# Schematic5.net
KiCad netlist of a schematic drawn in Altium Designer
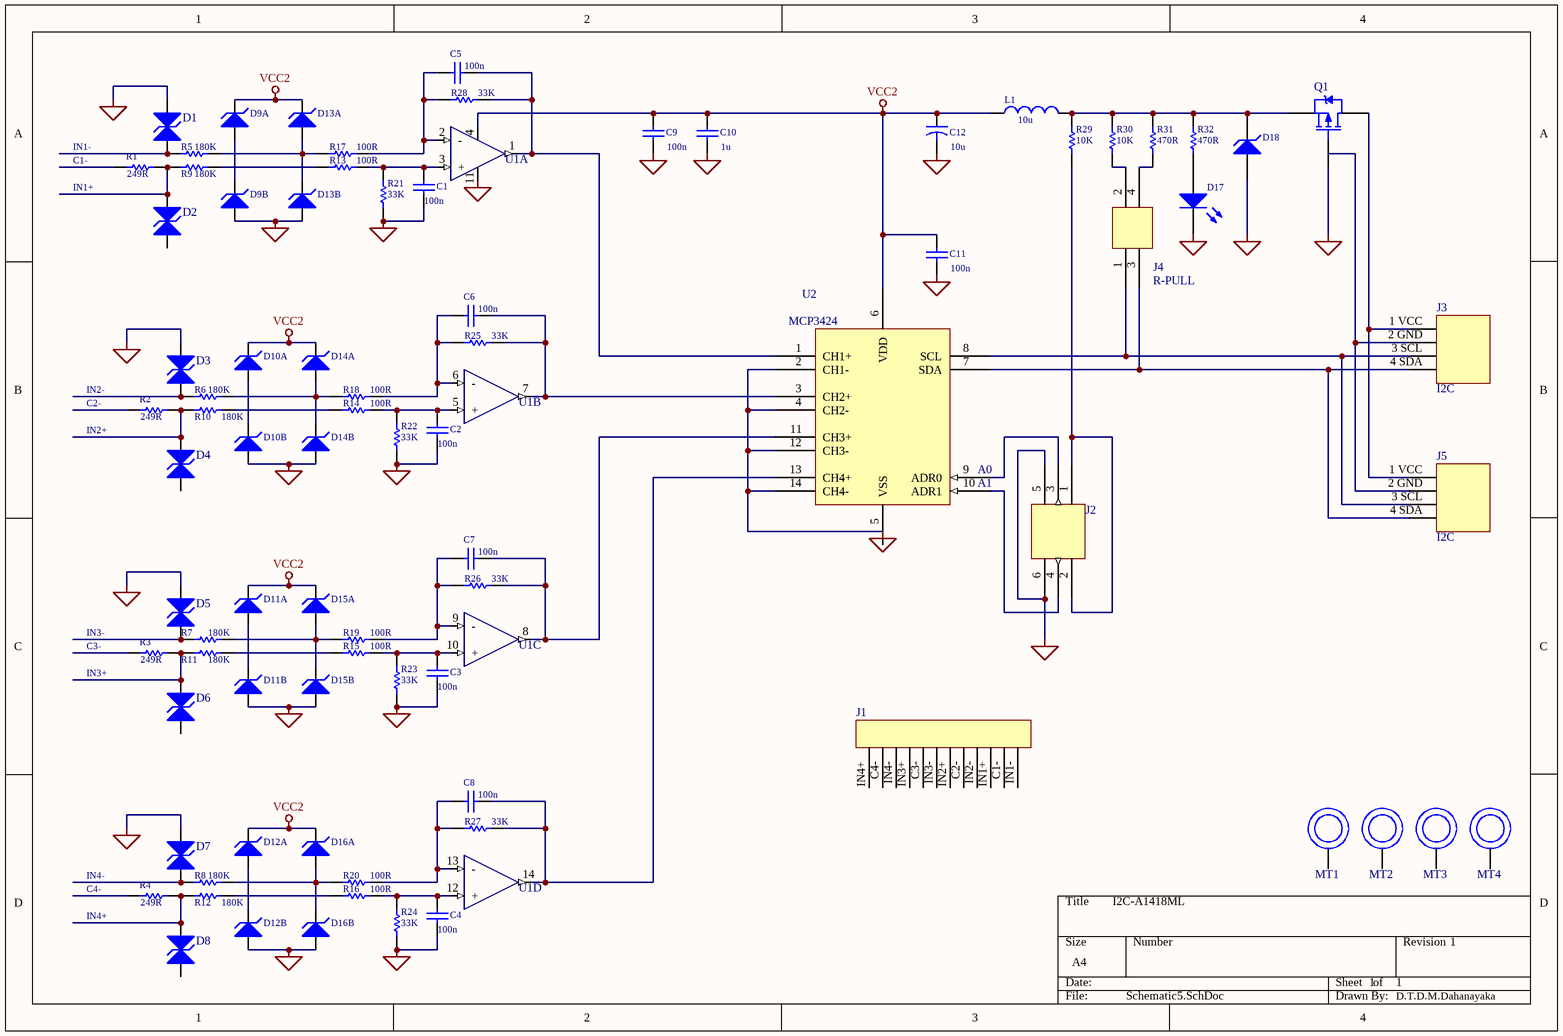
[diagram p0: Schematic5.SchDoc]

(export (version "E")
  (design (tool "Eeschema 10.0.6"))
  (components
    (comp (ref "C1")
      (value "100n")
      (footprint "RAD-0.3")
      (description "Capacitor")
      (fields (field (name "Comment") "Cap") (field (name "PUBLISHER") "Altium Limited"))
      (libsource (lib "Miscellaneous Devices") (part "Cap"))
    )
    (comp (ref "C2")
      (value "100n")
      (footprint "RAD-0.3")
      (description "Capacitor")
      (fields (field (name "Comment") "Cap") (field (name "PUBLISHER") "Altium Limited"))
      (libsource (lib "Miscellaneous Devices") (part "Cap"))
    )
    (comp (ref "C3")
      (value "100n")
      (footprint "RAD-0.3")
      (description "Capacitor")
      (fields (field (name "Comment") "Cap") (field (name "PUBLISHER") "Altium Limited"))
      (libsource (lib "Miscellaneous Devices") (part "Cap"))
    )
    (comp (ref "C4")
      (value "100n")
      (footprint "RAD-0.3")
      (description "Capacitor")
      (fields (field (name "Comment") "Cap") (field (name "PUBLISHER") "Altium Limited"))
      (libsource (lib "Miscellaneous Devices") (part "Cap"))
    )
    (comp (ref "C5")
      (value "100n")
      (footprint "RAD-0.3")
      (description "Capacitor")
      (fields (field (name "PUBLISHER") "Altium Limited"))
      (libsource (lib "Miscellaneous Devices") (part "Cap"))
    )
    (comp (ref "C6")
      (value "100n")
      (footprint "RAD-0.3")
      (description "Capacitor")
      (fields (field (name "PUBLISHER") "Altium Limited"))
      (libsource (lib "Miscellaneous Devices") (part "Cap"))
    )
    (comp (ref "C7")
      (value "100n")
      (footprint "RAD-0.3")
      (description "Capacitor")
      (fields (field (name "PUBLISHER") "Altium Limited"))
      (libsource (lib "Miscellaneous Devices") (part "Cap"))
    )
    (comp (ref "C8")
      (value "100n")
      (footprint "RAD-0.3")
      (description "Capacitor")
      (fields (field (name "PUBLISHER") "Altium Limited"))
      (libsource (lib "Miscellaneous Devices") (part "Cap"))
    )
    (comp (ref "C9")
      (value "100n")
      (footprint "RAD-0.3")
      (description "Capacitor")
      (fields (field (name "Comment") "Cap") (field (name "PUBLISHER") "Altium Limited"))
      (libsource (lib "Miscellaneous Devices") (part "Cap"))
    )
    (comp (ref "C10")
      (value "1u")
      (footprint "RAD-0.3")
      (description "Capacitor")
      (fields (field (name "Comment") "Cap") (field (name "PUBLISHER") "Altium Limited"))
      (libsource (lib "Miscellaneous Devices") (part "Cap"))
    )
    (comp (ref "C11")
      (value "100n")
      (footprint "RAD-0.3")
      (description "Capacitor")
      (fields (field (name "Comment") "Cap") (field (name "PUBLISHER") "Altium Limited"))
      (libsource (lib "Miscellaneous Devices") (part "Cap"))
    )
    (comp (ref "C12")
      (value "10u")
      (footprint "CAPR5-4X5")
      (description "Capacitor")
      (fields (field (name "Comment") "Cap2") (field (name "PUBLISHER") "Altium Limited"))
      (libsource (lib "Miscellaneous Devices") (part "Cap2"))
    )
    (comp (ref "D1")
      (value "~")
      (footprint "DO-41B")
      (description "Silicon Power Zener Diode")
      (fields (field (name "PUBLISHER") "Altium Limited"))
      (libsource (lib "") (part "ZY150_1"))
    )
    (comp (ref "D2")
      (value "~")
      (footprint "DO-41B")
      (description "Silicon Power Zener Diode")
      (fields (field (name "PUBLISHER") "Altium Limited"))
      (libsource (lib "Vishay Lite-On Discrete Diode") (part "ZY150"))
    )
    (comp (ref "D3")
      (value "~")
      (footprint "DO-41B")
      (description "Silicon Power Zener Diode")
      (fields (field (name "PUBLISHER") "Altium Limited"))
      (libsource (lib "") (part "ZY150_1"))
    )
    (comp (ref "D4")
      (value "~")
      (footprint "DO-41B")
      (description "Silicon Power Zener Diode")
      (fields (field (name "PUBLISHER") "Altium Limited"))
      (libsource (lib "Vishay Lite-On Discrete Diode") (part "ZY150"))
    )
    (comp (ref "D5")
      (value "~")
      (footprint "DO-41B")
      (description "Silicon Power Zener Diode")
      (fields (field (name "PUBLISHER") "Altium Limited"))
      (libsource (lib "") (part "ZY150_1"))
    )
    (comp (ref "D6")
      (value "~")
      (footprint "DO-41B")
      (description "Silicon Power Zener Diode")
      (fields (field (name "PUBLISHER") "Altium Limited"))
      (libsource (lib "Vishay Lite-On Discrete Diode") (part "ZY150"))
    )
    (comp (ref "D7")
      (value "~")
      (footprint "DO-41B")
      (description "Silicon Power Zener Diode")
      (fields (field (name "PUBLISHER") "Altium Limited"))
      (libsource (lib "") (part "ZY150_1"))
    )
    (comp (ref "D8")
      (value "~")
      (footprint "DO-41B")
      (description "Silicon Power Zener Diode")
      (fields (field (name "PUBLISHER") "Altium Limited"))
      (libsource (lib "Vishay Lite-On Discrete Diode") (part "ZY150"))
    )
    (comp (ref "D9A")
      (value "~")
      (footprint "DO-41B")
      (description "Silicon Power Zener Diode")
      (fields (field (name "PUBLISHER") "Altium Limited"))
      (libsource (lib "Vishay Lite-On Discrete Diode") (part "ZY150"))
    )
    (comp (ref "D9B")
      (value "~")
      (footprint "DO-41B")
      (description "Silicon Power Zener Diode")
      (fields (field (name "PUBLISHER") "Altium Limited"))
      (libsource (lib "Vishay Lite-On Discrete Diode") (part "ZY150"))
    )
    (comp (ref "D10A")
      (value "~")
      (footprint "DO-41B")
      (description "Silicon Power Zener Diode")
      (fields (field (name "PUBLISHER") "Altium Limited"))
      (libsource (lib "Vishay Lite-On Discrete Diode") (part "ZY150"))
    )
    (comp (ref "D10B")
      (value "~")
      (footprint "DO-41B")
      (description "Silicon Power Zener Diode")
      (fields (field (name "PUBLISHER") "Altium Limited"))
      (libsource (lib "Vishay Lite-On Discrete Diode") (part "ZY150"))
    )
    (comp (ref "D11")
      (value "ZY150")
      (footprint "DO-41B")
      (description "Silicon Power Zener Diode")
      (fields (field (name "PUBLISHER") "Altium Limited"))
      (libsource (lib "") (part "ZY150_1"))
    )
    (comp (ref "D11A")
      (value "~")
      (footprint "DO-41B")
      (description "Silicon Power Zener Diode")
      (fields (field (name "PUBLISHER") "Altium Limited"))
      (libsource (lib "Vishay Lite-On Discrete Diode") (part "ZY150"))
    )
    (comp (ref "D11B")
      (value "~")
      (footprint "DO-41B")
      (description "Silicon Power Zener Diode")
      (fields (field (name "PUBLISHER") "Altium Limited"))
      (libsource (lib "Vishay Lite-On Discrete Diode") (part "ZY150"))
    )
    (comp (ref "D12A")
      (value "~")
      (footprint "DO-41B")
      (description "Silicon Power Zener Diode")
      (fields (field (name "PUBLISHER") "Altium Limited"))
      (libsource (lib "Vishay Lite-On Discrete Diode") (part "ZY150"))
    )
    (comp (ref "D12B")
      (value "~")
      (footprint "DO-41B")
      (description "Silicon Power Zener Diode")
      (fields (field (name "PUBLISHER") "Altium Limited"))
      (libsource (lib "Vishay Lite-On Discrete Diode") (part "ZY150"))
    )
    (comp (ref "D13A")
      (value "~")
      (footprint "DO-41B")
      (description "Silicon Power Zener Diode")
      (fields (field (name "PUBLISHER") "Altium Limited"))
      (libsource (lib "Vishay Lite-On Discrete Diode") (part "ZY150"))
    )
    (comp (ref "D13B")
      (value "~")
      (footprint "DO-41B")
      (description "Silicon Power Zener Diode")
      (fields (field (name "PUBLISHER") "Altium Limited"))
      (libsource (lib "Vishay Lite-On Discrete Diode") (part "ZY150"))
    )
    (comp (ref "D14A")
      (value "~")
      (footprint "DO-41B")
      (description "Silicon Power Zener Diode")
      (fields (field (name "PUBLISHER") "Altium Limited"))
      (libsource (lib "Vishay Lite-On Discrete Diode") (part "ZY150"))
    )
    (comp (ref "D14B")
      (value "~")
      (footprint "DO-41B")
      (description "Silicon Power Zener Diode")
      (fields (field (name "PUBLISHER") "Altium Limited"))
      (libsource (lib "Vishay Lite-On Discrete Diode") (part "ZY150"))
    )
    (comp (ref "D15A")
      (value "~")
      (footprint "DO-41B")
      (description "Silicon Power Zener Diode")
      (fields (field (name "PUBLISHER") "Altium Limited"))
      (libsource (lib "Vishay Lite-On Discrete Diode") (part "ZY150"))
    )
    (comp (ref "D15B")
      (value "~")
      (footprint "DO-41B")
      (description "Silicon Power Zener Diode")
      (fields (field (name "PUBLISHER") "Altium Limited"))
      (libsource (lib "Vishay Lite-On Discrete Diode") (part "ZY150"))
    )
    (comp (ref "D16A")
      (value "~")
      (footprint "DO-41B")
      (description "Silicon Power Zener Diode")
      (fields (field (name "PUBLISHER") "Altium Limited"))
      (libsource (lib "Vishay Lite-On Discrete Diode") (part "ZY150"))
    )
    (comp (ref "D16B")
      (value "~")
      (footprint "DO-41B")
      (description "Silicon Power Zener Diode")
      (fields (field (name "PUBLISHER") "Altium Limited"))
      (libsource (lib "Vishay Lite-On Discrete Diode") (part "ZY150"))
    )
    (comp (ref "D17")
      (value "LED1")
      (footprint "LED-1")
      (description "Typical RED GaAs LED")
      (fields (field (name "PUBLISHER") "Altium Limited"))
      (libsource (lib "Miscellaneous Devices") (part "LED1"))
    )
    (comp (ref "D18")
      (value "~")
      (footprint "DO-41B")
      (description "Silicon Power Zener Diode")
      (fields (field (name "PUBLISHER") "Altium Limited"))
      (libsource (lib "") (part "ZY150_2"))
    )
    (comp (ref "D22")
      (value "~")
      (footprint "DO-41B")
      (description "Silicon Power Zener Diode")
      (fields (field (name "PUBLISHER") "Altium Limited"))
      (libsource (lib "") (part "ZY150_1"))
    )
    (comp (ref "D33")
      (value "ZY150")
      (footprint "DO-41B")
      (description "Silicon Power Zener Diode")
      (fields (field (name "PUBLISHER") "Altium Limited"))
      (libsource (lib "") (part "ZY150_1"))
    )
    (comp (ref "D44")
      (value "~")
      (footprint "DO-41B")
      (description "Silicon Power Zener Diode")
      (fields (field (name "PUBLISHER") "Altium Limited"))
      (libsource (lib "") (part "ZY150_1"))
    )
    (comp (ref "D55")
      (value "ZY150")
      (footprint "DO-41B")
      (description "Silicon Power Zener Diode")
      (fields (field (name "PUBLISHER") "Altium Limited"))
      (libsource (lib "") (part "ZY150_1"))
    )
    (comp (ref "D66")
      (value "~")
      (footprint "DO-41B")
      (description "Silicon Power Zener Diode")
      (fields (field (name "PUBLISHER") "Altium Limited"))
      (libsource (lib "") (part "ZY150_1"))
    )
    (comp (ref "D77")
      (value "ZY150")
      (footprint "DO-41B")
      (description "Silicon Power Zener Diode")
      (fields (field (name "PUBLISHER") "Altium Limited"))
      (libsource (lib "") (part "ZY150_1"))
    )
    (comp (ref "D88")
      (value "~")
      (footprint "DO-41B")
      (description "Silicon Power Zener Diode")
      (fields (field (name "PUBLISHER") "Altium Limited"))
      (libsource (lib "") (part "ZY150_1"))
    )
    (comp (ref "J1") (value "~") (libsource (lib "connector8") (part "Component_1")))
    (comp (ref "J2") (value "~") (libsource (lib "J2") (part "Component_1")))
    (comp (ref "J3") (value "I2C") (libsource (lib "J1") (part "Component_1")))
    (comp (ref "J4") (value "R-PULL") (libsource (lib "J3") (part "Component_1")))
    (comp (ref "J5") (value "I2C") (libsource (lib "J1") (part "Component_1")))
    (comp (ref "L1")
      (value "10u")
      (footprint "0402-A")
      (description "Inductor")
      (fields (field (name "PUBLISHER") "Altium Limited"))
      (libsource (lib "Miscellaneous Devices") (part "Inductor"))
    )
    (comp (ref "MT1") (value "Component_1") (libsource (lib "mt") (part "Component_1")))
    (comp (ref "MT2") (value "~") (libsource (lib "mt") (part "Component_1")))
    (comp (ref "MT3") (value "~") (libsource (lib "mt") (part "Component_1")))
    (comp (ref "MT4") (value "~") (libsource (lib "mt") (part "Component_1")))
    (comp (ref "Q1")
      (value "~")
      (footprint "TO-220AB")
      (description "P-Channel Power MOSFET")
      (fields (field (name "PUBLISHER") "Altium Limited"))
      (libsource (lib "Miscellaneous Devices") (part "PMOS-2"))
    )
    (comp (ref "R1")
      (value "249R")
      (footprint "AXIAL-0.3")
      (description "Resistor")
      (fields (field (name "PUBLISHER") "Altium Limited"))
      (libsource (lib "Miscellaneous Devices") (part "Res1"))
    )
    (comp (ref "R2")
      (value "249R")
      (footprint "AXIAL-0.3")
      (description "Resistor")
      (fields (field (name "PUBLISHER") "Altium Limited"))
      (libsource (lib "Miscellaneous Devices") (part "Res1"))
    )
    (comp (ref "R3")
      (value "249R")
      (footprint "AXIAL-0.3")
      (description "Resistor")
      (fields (field (name "PUBLISHER") "Altium Limited"))
      (libsource (lib "Miscellaneous Devices") (part "Res1"))
    )
    (comp (ref "R4")
      (value "249R")
      (footprint "AXIAL-0.3")
      (description "Resistor")
      (fields (field (name "PUBLISHER") "Altium Limited"))
      (libsource (lib "Miscellaneous Devices") (part "Res1"))
    )
    (comp (ref "R5")
      (value "180K")
      (footprint "AXIAL-0.3")
      (description "Resistor")
      (fields (field (name "PUBLISHER") "Altium Limited"))
      (libsource (lib "Miscellaneous Devices") (part "Res1"))
    )
    (comp (ref "R6")
      (value "180K")
      (footprint "AXIAL-0.3")
      (description "Resistor")
      (fields (field (name "PUBLISHER") "Altium Limited"))
      (libsource (lib "Miscellaneous Devices") (part "Res1"))
    )
    (comp (ref "R7")
      (value "180K")
      (footprint "AXIAL-0.3")
      (description "Resistor")
      (fields (field (name "PUBLISHER") "Altium Limited"))
      (libsource (lib "Miscellaneous Devices") (part "Res1"))
    )
    (comp (ref "R8")
      (value "180K")
      (footprint "AXIAL-0.3")
      (description "Resistor")
      (fields (field (name "PUBLISHER") "Altium Limited"))
      (libsource (lib "Miscellaneous Devices") (part "Res1"))
    )
    (comp (ref "R9")
      (value "180K")
      (footprint "AXIAL-0.3")
      (description "Resistor")
      (fields (field (name "PUBLISHER") "Altium Limited"))
      (libsource (lib "Miscellaneous Devices") (part "Res1"))
    )
    (comp (ref "R10")
      (value "180K")
      (footprint "AXIAL-0.3")
      (description "Resistor")
      (fields (field (name "PUBLISHER") "Altium Limited"))
      (libsource (lib "Miscellaneous Devices") (part "Res1"))
    )
    (comp (ref "R11")
      (value "180K")
      (footprint "AXIAL-0.3")
      (description "Resistor")
      (fields (field (name "PUBLISHER") "Altium Limited"))
      (libsource (lib "Miscellaneous Devices") (part "Res1"))
    )
    (comp (ref "R12")
      (value "180K")
      (footprint "AXIAL-0.3")
      (description "Resistor")
      (fields (field (name "PUBLISHER") "Altium Limited"))
      (libsource (lib "Miscellaneous Devices") (part "Res1"))
    )
    (comp (ref "R13")
      (value "100R")
      (footprint "AXIAL-0.3")
      (description "Resistor")
      (fields (field (name "PUBLISHER") "Altium Limited"))
      (libsource (lib "Miscellaneous Devices") (part "Res1"))
    )
    (comp (ref "R14")
      (value "100R")
      (footprint "AXIAL-0.3")
      (description "Resistor")
      (fields (field (name "PUBLISHER") "Altium Limited"))
      (libsource (lib "Miscellaneous Devices") (part "Res1"))
    )
    (comp (ref "R15")
      (value "100R")
      (footprint "AXIAL-0.3")
      (description "Resistor")
      (fields (field (name "PUBLISHER") "Altium Limited"))
      (libsource (lib "Miscellaneous Devices") (part "Res1"))
    )
    (comp (ref "R16")
      (value "100R")
      (footprint "AXIAL-0.3")
      (description "Resistor")
      (fields (field (name "PUBLISHER") "Altium Limited"))
      (libsource (lib "Miscellaneous Devices") (part "Res1"))
    )
    (comp (ref "R17")
      (value "100R")
      (footprint "AXIAL-0.3")
      (description "Resistor")
      (fields (field (name "PUBLISHER") "Altium Limited"))
      (libsource (lib "Miscellaneous Devices") (part "Res1"))
    )
    (comp (ref "R18")
      (value "100R")
      (footprint "AXIAL-0.3")
      (description "Resistor")
      (fields (field (name "PUBLISHER") "Altium Limited"))
      (libsource (lib "Miscellaneous Devices") (part "Res1"))
    )
    (comp (ref "R19")
      (value "100R")
      (footprint "AXIAL-0.3")
      (description "Resistor")
      (fields (field (name "PUBLISHER") "Altium Limited"))
      (libsource (lib "Miscellaneous Devices") (part "Res1"))
    )
    (comp (ref "R20")
      (value "100R")
      (footprint "AXIAL-0.3")
      (description "Resistor")
      (fields (field (name "PUBLISHER") "Altium Limited"))
      (libsource (lib "Miscellaneous Devices") (part "Res1"))
    )
    (comp (ref "R21")
      (value "33K")
      (footprint "AXIAL-0.3")
      (description "Resistor")
      (fields (field (name "PUBLISHER") "Altium Limited"))
      (libsource (lib "Miscellaneous Devices") (part "Res1"))
    )
    (comp (ref "R22")
      (value "33K")
      (footprint "AXIAL-0.3")
      (description "Resistor")
      (fields (field (name "PUBLISHER") "Altium Limited"))
      (libsource (lib "Miscellaneous Devices") (part "Res1"))
    )
    (comp (ref "R23")
      (value "33K")
      (footprint "AXIAL-0.3")
      (description "Resistor")
      (fields (field (name "PUBLISHER") "Altium Limited"))
      (libsource (lib "Miscellaneous Devices") (part "Res1"))
    )
    (comp (ref "R24")
      (value "33K")
      (footprint "AXIAL-0.3")
      (description "Resistor")
      (fields (field (name "PUBLISHER") "Altium Limited"))
      (libsource (lib "Miscellaneous Devices") (part "Res1"))
    )
    (comp (ref "R25")
      (value "33K")
      (footprint "AXIAL-0.3")
      (description "Resistor")
      (fields (field (name "PUBLISHER") "Altium Limited"))
      (libsource (lib "Miscellaneous Devices") (part "Res1"))
    )
    (comp (ref "R26")
      (value "33K")
      (footprint "AXIAL-0.3")
      (description "Resistor")
      (fields (field (name "PUBLISHER") "Altium Limited"))
      (libsource (lib "Miscellaneous Devices") (part "Res1"))
    )
    (comp (ref "R27")
      (value "33K")
      (footprint "AXIAL-0.3")
      (description "Resistor")
      (fields (field (name "PUBLISHER") "Altium Limited"))
      (libsource (lib "Miscellaneous Devices") (part "Res1"))
    )
    (comp (ref "R28")
      (value "33K")
      (footprint "AXIAL-0.3")
      (description "Resistor")
      (fields (field (name "PUBLISHER") "Altium Limited"))
      (libsource (lib "Miscellaneous Devices") (part "Res1"))
    )
    (comp (ref "R29")
      (value "10K")
      (footprint "AXIAL-0.3")
      (description "Resistor")
      (fields (field (name "PUBLISHER") "Altium Limited"))
      (libsource (lib "Miscellaneous Devices") (part "Res1"))
    )
    (comp (ref "R30")
      (value "10K")
      (footprint "AXIAL-0.3")
      (description "Resistor")
      (fields (field (name "PUBLISHER") "Altium Limited"))
      (libsource (lib "Miscellaneous Devices") (part "Res1"))
    )
    (comp (ref "R31")
      (value "470R")
      (footprint "AXIAL-0.3")
      (description "Resistor")
      (fields (field (name "PUBLISHER") "Altium Limited"))
      (libsource (lib "Miscellaneous Devices") (part "Res1"))
    )
    (comp (ref "R32")
      (value "470R")
      (footprint "AXIAL-0.3")
      (description "Resistor")
      (fields (field (name "PUBLISHER") "Altium Limited"))
      (libsource (lib "Miscellaneous Devices") (part "Res1"))
    )
    (comp (ref "U1A") (value "~") (libsource (lib "Op-Amp2") (part "Component_1")))
    (comp (ref "U1B") (value "~") (libsource (lib "") (part "Component_1_1")))
    (comp (ref "U1C") (value "~") (libsource (lib "Op-Amp1") (part "Component_1")))
    (comp (ref "U1D") (value "~") (libsource (lib "") (part "Component_1_2")))
    (comp (ref "U2") (value "MCP3424") (libsource (lib "12C-A1418ML") (part "Component_1")))
  )
  (nets
    (net (code "1") (name "<NO NET>") (class "Default")
      (node (ref "C1") (pin "1") (pinfunction "1_1") (pintype "passive"))
      (node (ref "C10") (pin "1") (pinfunction "1_1") (pintype "passive"))
      (node (ref "C11") (pin "1") (pinfunction "1_1") (pintype "passive"))
      (node (ref "C12") (pin "2") (pinfunction "2_2") (pintype "passive"))
      (node (ref "C2") (pin "1") (pinfunction "1_1") (pintype "passive"))
      (node (ref "C3") (pin "1") (pinfunction "1_1") (pintype "passive"))
      (node (ref "C4") (pin "1") (pinfunction "1_1") (pintype "passive"))
      (node (ref "C9") (pin "1") (pinfunction "1_1") (pintype "passive"))
      (node (ref "D1") (pin "1") (pinfunction "A_1") (pintype "passive"))
      (node (ref "D10B") (pin "1") (pinfunction "A_1") (pintype "passive"))
      (node (ref "D11B") (pin "1") (pinfunction "A_1") (pintype "passive"))
      (node (ref "D12B") (pin "1") (pinfunction "A_1") (pintype "passive"))
      (node (ref "D13B") (pin "1") (pinfunction "A_1") (pintype "passive"))
      (node (ref "D14B") (pin "1") (pinfunction "A_1") (pintype "passive"))
      (node (ref "D15B") (pin "1") (pinfunction "A_1") (pintype "passive"))
      (node (ref "D16B") (pin "1") (pinfunction "A_1") (pintype "passive"))
      (node (ref "D17") (pin "2") (pinfunction "K_2") (pintype "passive"))
      (node (ref "D18") (pin "1") (pinfunction "A_1") (pintype "passive"))
      (node (ref "D3") (pin "1") (pinfunction "A_1") (pintype "passive"))
      (node (ref "D5") (pin "1") (pinfunction "A_1") (pintype "passive"))
      (node (ref "D7") (pin "1") (pinfunction "A_1") (pintype "passive"))
      (node (ref "D9B") (pin "1") (pinfunction "A_1") (pintype "passive"))
      (node (ref "J2") (pin "5") (pintype "passive"))
      (node (ref "J2") (pin "6") (pintype "passive"))
      (node (ref "Q1") (pin "1") (pinfunction "G_1") (pintype "passive"))
      (node (ref "R21") (pin "1") (pinfunction "1_1") (pintype "passive"))
      (node (ref "R22") (pin "1") (pinfunction "1_1") (pintype "passive"))
      (node (ref "R23") (pin "1") (pinfunction "1_1") (pintype "passive"))
      (node (ref "R24") (pin "1") (pinfunction "1_1") (pintype "passive"))
      (node (ref "U1A") (pin "11") (pintype "passive"))
      (node (ref "U2") (pin "12") (pinfunction "CH3-_12") (pintype "passive"))
      (node (ref "U2") (pin "14") (pinfunction "CH4-_14") (pintype "passive"))
      (node (ref "U2") (pin "2") (pinfunction "CH1-_2") (pintype "passive"))
      (node (ref "U2") (pin "4") (pinfunction "CH2-_4") (pintype "passive"))
    )
    (net (code "2") (name "Net-(D1-K)") (class "Default")
      (node (ref "D1") (pin "2") (pinfunction "K_2") (pintype "passive"))
      (node (ref "D11") (pin "2") (pinfunction "K_2") (pintype "passive"))
    )
    (net (code "3") (name "Net-(D2-A)") (class "Default")
      (node (ref "D2") (pin "1") (pinfunction "A_1") (pintype "passive"))
      (node (ref "R1") (pin "2") (pinfunction "2_2") (pintype "passive"))
      (node (ref "R9") (pin "1") (pinfunction "1_1") (pintype "passive"))
    )
    (net (code "4") (name "Net-(D3-K)") (class "Default")
      (node (ref "D3") (pin "2") (pinfunction "K_2") (pintype "passive"))
      (node (ref "D33") (pin "2") (pinfunction "K_2") (pintype "passive"))
    )
    (net (code "5") (name "Net-(D4-A)") (class "Default")
      (node (ref "D4") (pin "1") (pinfunction "A_1") (pintype "passive"))
      (node (ref "R10") (pin "1") (pinfunction "1_1") (pintype "passive"))
      (node (ref "R2") (pin "2") (pinfunction "2_2") (pintype "passive"))
    )
    (net (code "6") (name "Net-(D5-K)") (class "Default")
      (node (ref "D5") (pin "2") (pinfunction "K_2") (pintype "passive"))
      (node (ref "D55") (pin "2") (pinfunction "K_2") (pintype "passive"))
    )
    (net (code "7") (name "Net-(D6-A)") (class "Default")
      (node (ref "D6") (pin "1") (pinfunction "A_1") (pintype "passive"))
      (node (ref "R11") (pin "1") (pinfunction "1_1") (pintype "passive"))
      (node (ref "R3") (pin "2") (pinfunction "2_2") (pintype "passive"))
    )
    (net (code "8") (name "Net-(D7-K)") (class "Default")
      (node (ref "D7") (pin "2") (pinfunction "K_2") (pintype "passive"))
      (node (ref "D77") (pin "2") (pinfunction "K_2") (pintype "passive"))
    )
    (net (code "9") (name "Net-(D8-A)") (class "Default")
      (node (ref "D8") (pin "1") (pinfunction "A_1") (pintype "passive"))
      (node (ref "R12") (pin "1") (pinfunction "1_1") (pintype "passive"))
      (node (ref "R4") (pin "2") (pinfunction "2_2") (pintype "passive"))
    )
    (net (code "10") (name "Net-(D9A-A)") (class "Default")
      (node (ref "D9A") (pin "1") (pinfunction "A_1") (pintype "passive"))
      (node (ref "D9B") (pin "2") (pinfunction "K_2") (pintype "passive"))
    )
    (net (code "11") (name "Net-(D10A-A)") (class "Default")
      (node (ref "D10A") (pin "1") (pinfunction "A_1") (pintype "passive"))
      (node (ref "D10B") (pin "2") (pinfunction "K_2") (pintype "passive"))
    )
    (net (code "12") (name "Net-(D11-A)") (class "Default")
      (node (ref "D11") (pin "1") (pinfunction "A_1") (pintype "passive"))
      (node (ref "R5") (pin "1") (pinfunction "1_1") (pintype "passive"))
    )
    (net (code "13") (name "Net-(D11A-A)") (class "Default")
      (node (ref "D11A") (pin "1") (pinfunction "A_1") (pintype "passive"))
      (node (ref "D11B") (pin "2") (pinfunction "K_2") (pintype "passive"))
    )
    (net (code "14") (name "Net-(D12A-A)") (class "Default")
      (node (ref "D12A") (pin "1") (pinfunction "A_1") (pintype "passive"))
      (node (ref "D12B") (pin "2") (pinfunction "K_2") (pintype "passive"))
    )
    (net (code "15") (name "Net-(D13A-A)") (class "Default")
      (node (ref "D13A") (pin "1") (pinfunction "A_1") (pintype "passive"))
      (node (ref "D13B") (pin "2") (pinfunction "K_2") (pintype "passive"))
      (node (ref "R17") (pin "1") (pinfunction "1_1") (pintype "passive"))
      (node (ref "R5") (pin "2") (pinfunction "2_2") (pintype "passive"))
    )
    (net (code "16") (name "Net-(D14A-A)") (class "Default")
      (node (ref "D14A") (pin "1") (pinfunction "A_1") (pintype "passive"))
      (node (ref "D14B") (pin "2") (pinfunction "K_2") (pintype "passive"))
      (node (ref "R18") (pin "1") (pinfunction "1_1") (pintype "passive"))
      (node (ref "R6") (pin "2") (pinfunction "2_2") (pintype "passive"))
    )
    (net (code "17") (name "Net-(D15A-A)") (class "Default")
      (node (ref "D15A") (pin "1") (pinfunction "A_1") (pintype "passive"))
      (node (ref "D15B") (pin "2") (pinfunction "K_2") (pintype "passive"))
      (node (ref "R19") (pin "1") (pinfunction "1_1") (pintype "passive"))
      (node (ref "R7") (pin "2") (pinfunction "2_2") (pintype "passive"))
    )
    (net (code "18") (name "Net-(D16A-A)") (class "Default")
      (node (ref "D16A") (pin "1") (pinfunction "A_1") (pintype "passive"))
      (node (ref "D16B") (pin "2") (pinfunction "K_2") (pintype "passive"))
      (node (ref "R20") (pin "1") (pinfunction "1_1") (pintype "passive"))
      (node (ref "R8") (pin "2") (pinfunction "2_2") (pintype "passive"))
    )
    (net (code "19") (name "Net-(D17-A)") (class "Default")
      (node (ref "D17") (pin "1") (pinfunction "A_1") (pintype "passive"))
      (node (ref "R32") (pin "1") (pinfunction "1_1") (pintype "passive"))
    )
    (net (code "20") (name "Net-(D18-K)") (class "Default")
      (node (ref "D18") (pin "2") (pinfunction "K_2") (pintype "passive"))
      (node (ref "L1") (pin "2") (pinfunction "2_2") (pintype "passive"))
      (node (ref "Q1") (pin "3") (pinfunction "S_3") (pintype "passive"))
      (node (ref "R29") (pin "2") (pinfunction "2_2") (pintype "passive"))
      (node (ref "R30") (pin "2") (pinfunction "2_2") (pintype "passive"))
      (node (ref "R31") (pin "2") (pinfunction "2_2") (pintype "passive"))
      (node (ref "R32") (pin "2") (pinfunction "2_2") (pintype "passive"))
    )
    (net (code "21") (name "Net-(D33-A)") (class "Default")
      (node (ref "D33") (pin "1") (pinfunction "A_1") (pintype "passive"))
      (node (ref "R6") (pin "1") (pinfunction "1_1") (pintype "passive"))
    )
    (net (code "22") (name "Net-(D55-A)") (class "Default")
      (node (ref "D55") (pin "1") (pinfunction "A_1") (pintype "passive"))
      (node (ref "R7") (pin "1") (pinfunction "1_1") (pintype "passive"))
    )
    (net (code "23") (name "Net-(D77-A)") (class "Default")
      (node (ref "D77") (pin "1") (pinfunction "A_1") (pintype "passive"))
      (node (ref "R8") (pin "1") (pinfunction "1_1") (pintype "passive"))
    )
    (net (code "24") (name "Net-(J2-Pad1)") (class "Default")
      (node (ref "J2") (pin "1") (pintype "passive"))
      (node (ref "J2") (pin "2") (pintype "passive"))
      (node (ref "R29") (pin "1") (pinfunction "1_1") (pintype "passive"))
    )
    (net (code "25") (name "Net-(J3-Pad2_GND)") (class "Default")
      (node (ref "J3") (pin "2_GND") (pintype "passive"))
      (node (ref "J5") (pin "2_GND") (pintype "passive"))
    )
    (net (code "26") (name "Net-(J4-Pad2)") (class "Default")
      (node (ref "J4") (pin "2") (pintype "passive"))
      (node (ref "R30") (pin "1") (pinfunction "1_1") (pintype "passive"))
    )
    (net (code "27") (name "Net-(J4-Pad4)") (class "Default")
      (node (ref "J4") (pin "4") (pintype "passive"))
      (node (ref "R31") (pin "1") (pinfunction "1_1") (pintype "passive"))
    )
    (net (code "28") (name "Net-(Q1-D)") (class "Default")
      (node (ref "J3") (pin "1_VCC") (pintype "passive"))
      (node (ref "J5") (pin "1_VCC") (pintype "passive"))
      (node (ref "Q1") (pin "2") (pinfunction "D_2") (pintype "passive"))
    )
    (net (code "29") (name "Net-(R10-Pad2)") (class "Default")
      (node (ref "R10") (pin "2") (pinfunction "2_2") (pintype "passive"))
      (node (ref "R14") (pin "1") (pinfunction "1_1") (pintype "passive"))
    )
    (net (code "30") (name "Net-(R11-Pad2)") (class "Default")
      (node (ref "R11") (pin "2") (pinfunction "2_2") (pintype "passive"))
      (node (ref "R15") (pin "1") (pinfunction "1_1") (pintype "passive"))
    )
    (net (code "31") (name "Net-(R12-Pad2)") (class "Default")
      (node (ref "R12") (pin "2") (pinfunction "2_2") (pintype "passive"))
      (node (ref "R16") (pin "1") (pinfunction "1_1") (pintype "passive"))
    )
    (net (code "32") (name "Net-(R13-Pad1)") (class "Default")
      (node (ref "R13") (pin "1") (pinfunction "1_1") (pintype "passive"))
      (node (ref "R9") (pin "2") (pinfunction "2_2") (pintype "passive"))
    )
    (net (code "33") (name "Net-(U1A-+)") (class "Default")
      (node (ref "C1") (pin "2") (pinfunction "2_2") (pintype "passive"))
      (node (ref "R13") (pin "2") (pinfunction "2_2") (pintype "passive"))
      (node (ref "R21") (pin "2") (pinfunction "2_2") (pintype "passive"))
      (node (ref "U1A") (pin "3") (pinfunction "+_3") (pintype "input"))
    )
    (net (code "34") (name "Net-(U1A--)") (class "Default")
      (node (ref "C5") (pin "1") (pinfunction "1_1") (pintype "passive"))
      (node (ref "R17") (pin "2") (pinfunction "2_2") (pintype "passive"))
      (node (ref "R28") (pin "1") (pinfunction "1_1") (pintype "passive"))
      (node (ref "U1A") (pin "2") (pinfunction "-_2") (pintype "input"))
    )
    (net (code "35") (name "Net-(U1B-+)") (class "Default")
      (node (ref "C2") (pin "2") (pinfunction "2_2") (pintype "passive"))
      (node (ref "R14") (pin "2") (pinfunction "2_2") (pintype "passive"))
      (node (ref "R22") (pin "2") (pinfunction "2_2") (pintype "passive"))
      (node (ref "U1B") (pin "5") (pinfunction "+_5") (pintype "input"))
    )
    (net (code "36") (name "Net-(U1B--)") (class "Default")
      (node (ref "C6") (pin "1") (pinfunction "1_1") (pintype "passive"))
      (node (ref "R18") (pin "2") (pinfunction "2_2") (pintype "passive"))
      (node (ref "R25") (pin "1") (pinfunction "1_1") (pintype "passive"))
      (node (ref "U1B") (pin "6") (pinfunction "-_6") (pintype "input"))
    )
    (net (code "37") (name "Net-(U1C-+)") (class "Default")
      (node (ref "C3") (pin "2") (pinfunction "2_2") (pintype "passive"))
      (node (ref "R15") (pin "2") (pinfunction "2_2") (pintype "passive"))
      (node (ref "R23") (pin "2") (pinfunction "2_2") (pintype "passive"))
      (node (ref "U1C") (pin "10") (pinfunction "+_10") (pintype "input"))
    )
    (net (code "38") (name "Net-(U1C--)") (class "Default")
      (node (ref "C7") (pin "1") (pinfunction "1_1") (pintype "passive"))
      (node (ref "R19") (pin "2") (pinfunction "2_2") (pintype "passive"))
      (node (ref "R26") (pin "1") (pinfunction "1_1") (pintype "passive"))
      (node (ref "U1C") (pin "9") (pinfunction "-_9") (pintype "input"))
    )
    (net (code "39") (name "Net-(U1D-+)") (class "Default")
      (node (ref "C4") (pin "2") (pinfunction "2_2") (pintype "passive"))
      (node (ref "R16") (pin "2") (pinfunction "2_2") (pintype "passive"))
      (node (ref "R24") (pin "2") (pinfunction "2_2") (pintype "passive"))
      (node (ref "U1D") (pin "12") (pinfunction "+_12") (pintype "input"))
    )
    (net (code "40") (name "Net-(U1D--)") (class "Default")
      (node (ref "C8") (pin "1") (pinfunction "1_1") (pintype "passive"))
      (node (ref "R20") (pin "2") (pinfunction "2_2") (pintype "passive"))
      (node (ref "R27") (pin "1") (pinfunction "1_1") (pintype "passive"))
      (node (ref "U1D") (pin "13") (pinfunction "-_13") (pintype "input"))
    )
    (net (code "41") (name "Net-(U2-ADR0)") (class "Default")
      (node (ref "J2") (pin "3") (pintype "output"))
      (node (ref "U2") (pin "9") (pinfunction "ADR0_9") (pintype "input"))
    )
    (net (code "42") (name "Net-(U2-ADR1)") (class "Default")
      (node (ref "J2") (pin "4") (pintype "output"))
      (node (ref "U2") (pin "10") (pinfunction "ADR1_10") (pintype "input"))
    )
    (net (code "43") (name "Net-(U2-CH1+)") (class "Default")
      (node (ref "C5") (pin "2") (pinfunction "2_2") (pintype "passive"))
      (node (ref "R28") (pin "2") (pinfunction "2_2") (pintype "passive"))
      (node (ref "U1A") (pin "1") (pintype "output"))
      (node (ref "U2") (pin "1") (pinfunction "CH1+_1") (pintype "passive"))
    )
    (net (code "44") (name "Net-(U2-CH2+)") (class "Default")
      (node (ref "C6") (pin "2") (pinfunction "2_2") (pintype "passive"))
      (node (ref "R25") (pin "2") (pinfunction "2_2") (pintype "passive"))
      (node (ref "U1B") (pin "7") (pintype "output"))
      (node (ref "U2") (pin "3") (pinfunction "CH2+_3") (pintype "passive"))
    )
    (net (code "45") (name "Net-(U2-CH3+)") (class "Default")
      (node (ref "C7") (pin "2") (pinfunction "2_2") (pintype "passive"))
      (node (ref "R26") (pin "2") (pinfunction "2_2") (pintype "passive"))
      (node (ref "U1C") (pin "8") (pintype "output"))
      (node (ref "U2") (pin "11") (pinfunction "CH3+_11") (pintype "passive"))
    )
    (net (code "46") (name "Net-(U2-CH4+)") (class "Default")
      (node (ref "C8") (pin "2") (pinfunction "2_2") (pintype "passive"))
      (node (ref "R27") (pin "2") (pinfunction "2_2") (pintype "passive"))
      (node (ref "U1D") (pin "14") (pintype "output"))
      (node (ref "U2") (pin "13") (pinfunction "CH4+_13") (pintype "passive"))
    )
    (net (code "47") (name "Net-(U2-SCL)") (class "Default")
      (node (ref "J3") (pin "3_SCL") (pintype "passive"))
      (node (ref "J4") (pin "1") (pintype "passive"))
      (node (ref "J5") (pin "3_SCL") (pintype "passive"))
      (node (ref "U2") (pin "8") (pinfunction "SCL_8") (pintype "passive"))
    )
    (net (code "48") (name "Net-(U2-SDA)") (class "Default")
      (node (ref "J3") (pin "4_SDA") (pintype "passive"))
      (node (ref "J4") (pin "3") (pintype "passive"))
      (node (ref "J5") (pin "4_SDA") (pintype "passive"))
      (node (ref "U2") (pin "7") (pinfunction "SDA_7") (pintype "passive"))
    )
    (net (code "49") (name "VCC2") (class "Default")
      (node (ref "C10") (pin "2") (pinfunction "2_2") (pintype "passive"))
      (node (ref "C11") (pin "2") (pinfunction "2_2") (pintype "passive"))
      (node (ref "C12") (pin "1") (pinfunction "1_1") (pintype "passive"))
      (node (ref "C9") (pin "2") (pinfunction "2_2") (pintype "passive"))
      (node (ref "D10A") (pin "2") (pinfunction "K_2") (pintype "passive"))
      (node (ref "D11A") (pin "2") (pinfunction "K_2") (pintype "passive"))
      (node (ref "D12A") (pin "2") (pinfunction "K_2") (pintype "passive"))
      (node (ref "D13A") (pin "2") (pinfunction "K_2") (pintype "passive"))
      (node (ref "D14A") (pin "2") (pinfunction "K_2") (pintype "passive"))
      (node (ref "D15A") (pin "2") (pinfunction "K_2") (pintype "passive"))
      (node (ref "D16A") (pin "2") (pinfunction "K_2") (pintype "passive"))
      (node (ref "D9A") (pin "2") (pinfunction "K_2") (pintype "passive"))
      (node (ref "L1") (pin "1") (pinfunction "1_1") (pintype "passive"))
      (node (ref "U1A") (pin "4") (pintype "passive"))
      (node (ref "U2") (pin "6") (pinfunction "VDD_6") (pintype "passive"))
    )
    (net (code "50") (name "unconnected-(D2-K-Pad2)") (class "Default")
      (node (ref "D2") (pin "2") (pinfunction "K_2") (pintype "passive"))
    )
    (net (code "51") (name "unconnected-(D4-K-Pad2)") (class "Default")
      (node (ref "D4") (pin "2") (pinfunction "K_2") (pintype "passive"))
    )
    (net (code "52") (name "unconnected-(D6-K-Pad2)") (class "Default")
      (node (ref "D6") (pin "2") (pinfunction "K_2") (pintype "passive"))
    )
    (net (code "53") (name "unconnected-(D8-K-Pad2)") (class "Default")
      (node (ref "D8") (pin "2") (pinfunction "K_2") (pintype "passive"))
    )
    (net (code "54") (name "unconnected-(D22-A-Pad1)") (class "Default")
      (node (ref "D22") (pin "1") (pinfunction "A_1") (pintype "passive"))
    )
    (net (code "55") (name "unconnected-(D22-K-Pad2)") (class "Default")
      (node (ref "D22") (pin "2") (pinfunction "K_2") (pintype "passive"))
    )
    (net (code "56") (name "unconnected-(D44-A-Pad1)") (class "Default")
      (node (ref "D44") (pin "1") (pinfunction "A_1") (pintype "passive"))
    )
    (net (code "57") (name "unconnected-(D44-K-Pad2)") (class "Default")
      (node (ref "D44") (pin "2") (pinfunction "K_2") (pintype "passive"))
    )
    (net (code "58") (name "unconnected-(D66-A-Pad1)") (class "Default")
      (node (ref "D66") (pin "1") (pinfunction "A_1") (pintype "passive"))
    )
    (net (code "59") (name "unconnected-(D66-K-Pad2)") (class "Default")
      (node (ref "D66") (pin "2") (pinfunction "K_2") (pintype "passive"))
    )
    (net (code "60") (name "unconnected-(D88-A-Pad1)") (class "Default")
      (node (ref "D88") (pin "1") (pinfunction "A_1") (pintype "passive"))
    )
    (net (code "61") (name "unconnected-(D88-K-Pad2)") (class "Default")
      (node (ref "D88") (pin "2") (pinfunction "K_2") (pintype "passive"))
    )
    (net (code "62") (name "unconnected-(J1-PadC1-)") (class "Default")
      (node (ref "J1") (pin "C1-") (pintype "passive"))
    )
    (net (code "63") (name "unconnected-(J1-PadC2-)") (class "Default")
      (node (ref "J1") (pin "C2-") (pintype "passive"))
    )
    (net (code "64") (name "unconnected-(J1-PadC3-)") (class "Default")
      (node (ref "J1") (pin "C3-") (pintype "passive"))
    )
    (net (code "65") (name "unconnected-(J1-PadC4-)") (class "Default")
      (node (ref "J1") (pin "C4-") (pintype "passive"))
    )
    (net (code "66") (name "unconnected-(J1-PadIN1+)") (class "Default")
      (node (ref "J1") (pin "IN1+") (pintype "passive"))
    )
    (net (code "67") (name "unconnected-(J1-PadIN1-)") (class "Default")
      (node (ref "J1") (pin "IN1-") (pintype "passive"))
    )
    (net (code "68") (name "unconnected-(J1-PadIN2+)") (class "Default")
      (node (ref "J1") (pin "IN2+") (pintype "passive"))
    )
    (net (code "69") (name "unconnected-(J1-PadIN2-)") (class "Default")
      (node (ref "J1") (pin "IN2-") (pintype "passive"))
    )
    (net (code "70") (name "unconnected-(J1-PadIN3+)") (class "Default")
      (node (ref "J1") (pin "IN3+") (pintype "passive"))
    )
    (net (code "71") (name "unconnected-(J1-PadIN3-)") (class "Default")
      (node (ref "J1") (pin "IN3-") (pintype "passive"))
    )
    (net (code "72") (name "unconnected-(J1-PadIN4+)") (class "Default")
      (node (ref "J1") (pin "IN4+") (pintype "passive"))
    )
    (net (code "73") (name "unconnected-(J1-PadIN4-)") (class "Default")
      (node (ref "J1") (pin "IN4-") (pintype "passive"))
    )
    (net (code "74") (name "unconnected-(MT1-Pad)") (class "Default")
      (node (ref "MT1") (pin "") (pintype "power_in"))
    )
    (net (code "75") (name "unconnected-(MT2-Pad)") (class "Default")
      (node (ref "MT2") (pin "") (pintype "power_in"))
    )
    (net (code "76") (name "unconnected-(MT3-Pad)") (class "Default")
      (node (ref "MT3") (pin "") (pintype "power_in"))
    )
    (net (code "77") (name "unconnected-(MT4-Pad)") (class "Default")
      (node (ref "MT4") (pin "") (pintype "power_in"))
    )
    (net (code "78") (name "unconnected-(R1-Pad1)") (class "Default")
      (node (ref "R1") (pin "1") (pinfunction "1_1") (pintype "passive"))
    )
    (net (code "79") (name "unconnected-(R2-Pad1)") (class "Default")
      (node (ref "R2") (pin "1") (pinfunction "1_1") (pintype "passive"))
    )
    (net (code "80") (name "unconnected-(R3-Pad1)") (class "Default")
      (node (ref "R3") (pin "1") (pinfunction "1_1") (pintype "passive"))
    )
    (net (code "81") (name "unconnected-(R4-Pad1)") (class "Default")
      (node (ref "R4") (pin "1") (pinfunction "1_1") (pintype "passive"))
    )
    (net (code "82") (name "unconnected-(U2-VSS-Pad5)") (class "Default")
      (node (ref "U2") (pin "5") (pinfunction "VSS_5") (pintype "passive"))
    )
  )
)
